# XBEE.net
KiCad netlist of a schematic drawn in Altium Designer
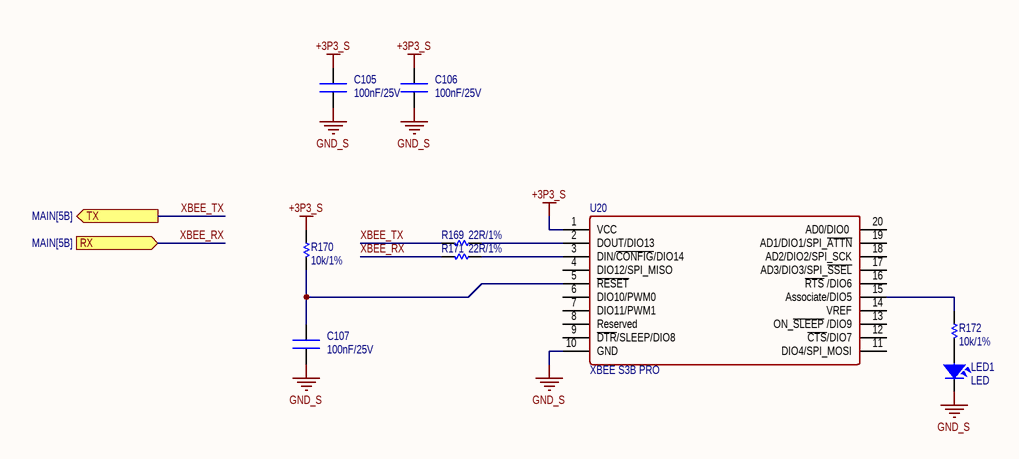
[diagram p0: XBEE.SchDoc]

(export (version "E")
  (design (tool "Eeschema 10.0.6"))
  (components
    (comp (ref "C105")
      (value "100nF/25V")
      (footprint "CN-SMD-0603")
      (description "CL10B104KA8NNNC")
      (libsource (lib "Library") (part "CN"))
    )
    (comp (ref "C106")
      (value "100nF/25V")
      (footprint "CN-SMD-0603")
      (description "CL10B104KA8NNNC")
      (libsource (lib "Library") (part "CN"))
    )
    (comp (ref "C107")
      (value "100nF/25V")
      (footprint "CN-SMD-0603")
      (description "CL10B104KA8NNNC")
      (libsource (lib "Library") (part "CN"))
    )
    (comp (ref "LED1") (value "LED") (footprint "LED-0805-Red") (libsource (lib "Library") (part "LED SMD")))
    (comp (ref "R169")
      (value "22R/1%")
      (footprint "RES-SMD-0603")
      (description "ERJ-3EKF22R0V")
      (libsource (lib "Library") (part "Res-SMD"))
    )
    (comp (ref "R170")
      (value "10k/1%")
      (footprint "RES-SMD-0603")
      (description "ERJ-3EKF1002V")
      (fields
        (field (name "MANUFACTURER") "Generic Components")
        (field (name "PUBLISHER") "Altium Hobart Technology Centre")
      )
      (libsource (lib "Library") (part "Res-SMD"))
    )
    (comp (ref "R171")
      (value "22R/1%")
      (footprint "RES-SMD-0603")
      (description "ERJ-3EKF22R0V")
      (libsource (lib "Library") (part "Res-SMD"))
    )
    (comp (ref "R172")
      (value "10k/1%")
      (footprint "RES-SMD-0603")
      (description "ERJ-3EKF1002V")
      (fields
        (field (name "MANUFACTURER") "Generic Components")
        (field (name "PUBLISHER") "Altium Hobart Technology Centre")
      )
      (libsource (lib "Library") (part "Res-SMD"))
    )
    (comp (ref "U20")
      (value "XBEE S3B PRO")
      (footprint "XBEE S3B PRO DIP")
      (libsource (lib "Library") (part "XBEE S3B PRO"))
    )
  )
  (nets
    (net (code "1") (name "+3P3_S") (class "Default")
      (node (ref "C105") (pin "2") (pinfunction "2_2") (pintype "passive"))
      (node (ref "C106") (pin "2") (pinfunction "2_2") (pintype "passive"))
      (node (ref "R170") (pin "1") (pinfunction "1_1") (pintype "passive"))
      (node (ref "U20") (pin "1") (pinfunction "VCC_1") (pintype "passive"))
    )
    (net (code "2") (name "/XBEE_RX") (class "Default")
      (node (ref "R171") (pin "2") (pinfunction "2_2") (pintype "passive"))
    )
    (net (code "3") (name "/XBEE_TX") (class "Default")
      (node (ref "R169") (pin "2") (pinfunction "2_2") (pintype "passive"))
    )
    (net (code "4") (name "GND_S") (class "Default")
      (node (ref "C105") (pin "1") (pinfunction "1_1") (pintype "passive"))
      (node (ref "C106") (pin "1") (pinfunction "1_1") (pintype "passive"))
      (node (ref "C107") (pin "1") (pinfunction "1_1") (pintype "passive"))
      (node (ref "LED1") (pin "2") (pinfunction "2_2") (pintype "passive"))
      (node (ref "U20") (pin "10") (pinfunction "GND_10") (pintype "passive"))
    )
    (net (code "5") (name "Net-(LED1-Pad1)") (class "Default")
      (node (ref "LED1") (pin "1") (pinfunction "1_1") (pintype "passive"))
      (node (ref "R172") (pin "2") (pinfunction "2_2") (pintype "passive"))
    )
    (net (code "6") (name "Net-(U20-Associate{slash}DIO5)") (class "Default")
      (node (ref "R172") (pin "1") (pinfunction "1_1") (pintype "passive"))
      (node (ref "U20") (pin "15") (pinfunction "Associate/DIO5_15") (pintype "passive"))
    )
    (net (code "7") (name "Net-(U20-DIN{slash}~{CONFIG}{slash}DIO14)") (class "Default")
      (node (ref "R171") (pin "1") (pinfunction "1_1") (pintype "passive"))
      (node (ref "U20") (pin "3") (pinfunction "DIN/~{CONFIG}/DIO14_3") (pintype "passive"))
    )
    (net (code "8") (name "Net-(U20-DOUT{slash}DIO13)") (class "Default")
      (node (ref "R169") (pin "1") (pinfunction "1_1") (pintype "passive"))
      (node (ref "U20") (pin "2") (pinfunction "DOUT/DIO13_2") (pintype "passive"))
    )
    (net (code "9") (name "Net-(U20-~{RESET})") (class "Default")
      (node (ref "C107") (pin "2") (pinfunction "2_2") (pintype "passive"))
      (node (ref "R170") (pin "2") (pinfunction "2_2") (pintype "passive"))
      (node (ref "U20") (pin "5") (pinfunction "~{RESET}_5") (pintype "passive"))
    )
    (net (code "10") (name "unconnected-(U20-AD0{slash}DIO0-Pad20)") (class "Default")
      (node (ref "U20") (pin "20") (pinfunction "AD0/DIO0_20") (pintype "passive"))
    )
    (net (code "11") (name "unconnected-(U20-AD1{slash}DIO1{slash}SPI_~{ATTN}-Pad19)") (class "Default")
      (node (ref "U20") (pin "19") (pinfunction "AD1/DIO1/SPI_~{ATTN}_19") (pintype "passive"))
    )
    (net (code "12") (name "unconnected-(U20-AD2{slash}DIO2{slash}SPI_SCK-Pad18)") (class "Default")
      (node (ref "U20") (pin "18") (pinfunction "AD2/DIO2/SPI_SCK_18") (pintype "passive"))
    )
    (net (code "13") (name "unconnected-(U20-AD3{slash}DIO3{slash}SPI_~{SSEL}-Pad17)") (class "Default")
      (node (ref "U20") (pin "17") (pinfunction "AD3/DIO3/SPI_~{SSEL}_17") (pintype "passive"))
    )
    (net (code "14") (name "unconnected-(U20-DIO4{slash}SPI_MOSI-Pad11)") (class "Default")
      (node (ref "U20") (pin "11") (pinfunction "DIO4/SPI_MOSI_11") (pintype "passive"))
    )
    (net (code "15") (name "unconnected-(U20-DIO10{slash}PWM0-Pad6)") (class "Default")
      (node (ref "U20") (pin "6") (pinfunction "DIO10/PWM0_6") (pintype "passive"))
    )
    (net (code "16") (name "unconnected-(U20-DIO11{slash}PWM1-Pad7)") (class "Default")
      (node (ref "U20") (pin "7") (pinfunction "DIO11/PWM1_7") (pintype "passive"))
    )
    (net (code "17") (name "unconnected-(U20-DIO12{slash}SPI_MISO-Pad4)") (class "Default")
      (node (ref "U20") (pin "4") (pinfunction "DIO12/SPI_MISO_4") (pintype "passive"))
    )
    (net (code "18") (name "unconnected-(U20-ON_~{SLEEP}_{slash}DIO9-Pad13)") (class "Default")
      (node (ref "U20") (pin "13") (pinfunction "ON_~{SLEEP}_/DIO9_13") (pintype "passive"))
    )
    (net (code "19") (name "unconnected-(U20-Reserved-Pad8)") (class "Default")
      (node (ref "U20") (pin "8") (pinfunction "Reserved_8") (pintype "passive"))
    )
    (net (code "20") (name "unconnected-(U20-VREF-Pad14)") (class "Default")
      (node (ref "U20") (pin "14") (pinfunction "VREF_14") (pintype "passive"))
    )
    (net (code "21") (name "unconnected-(U20-~{CTS}{slash}DIO7-Pad12)") (class "Default")
      (node (ref "U20") (pin "12") (pinfunction "~{CTS}/DIO7_12") (pintype "passive"))
    )
    (net (code "22") (name "unconnected-(U20-~{DTR}{slash}SLEEP{slash}DIO8-Pad9)") (class "Default")
      (node (ref "U20") (pin "9") (pinfunction "~{DTR}/SLEEP/DIO8_9") (pintype "passive"))
    )
    (net (code "23") (name "unconnected-(U20-~{RTS}_{slash}DIO6-Pad16)") (class "Default")
      (node (ref "U20") (pin "16") (pinfunction "~{RTS}_/DIO6_16") (pintype "passive"))
    )
  )
)
